# OSPLC2_2_IO4.net
KiCad netlist of a schematic drawn in Altium Designer
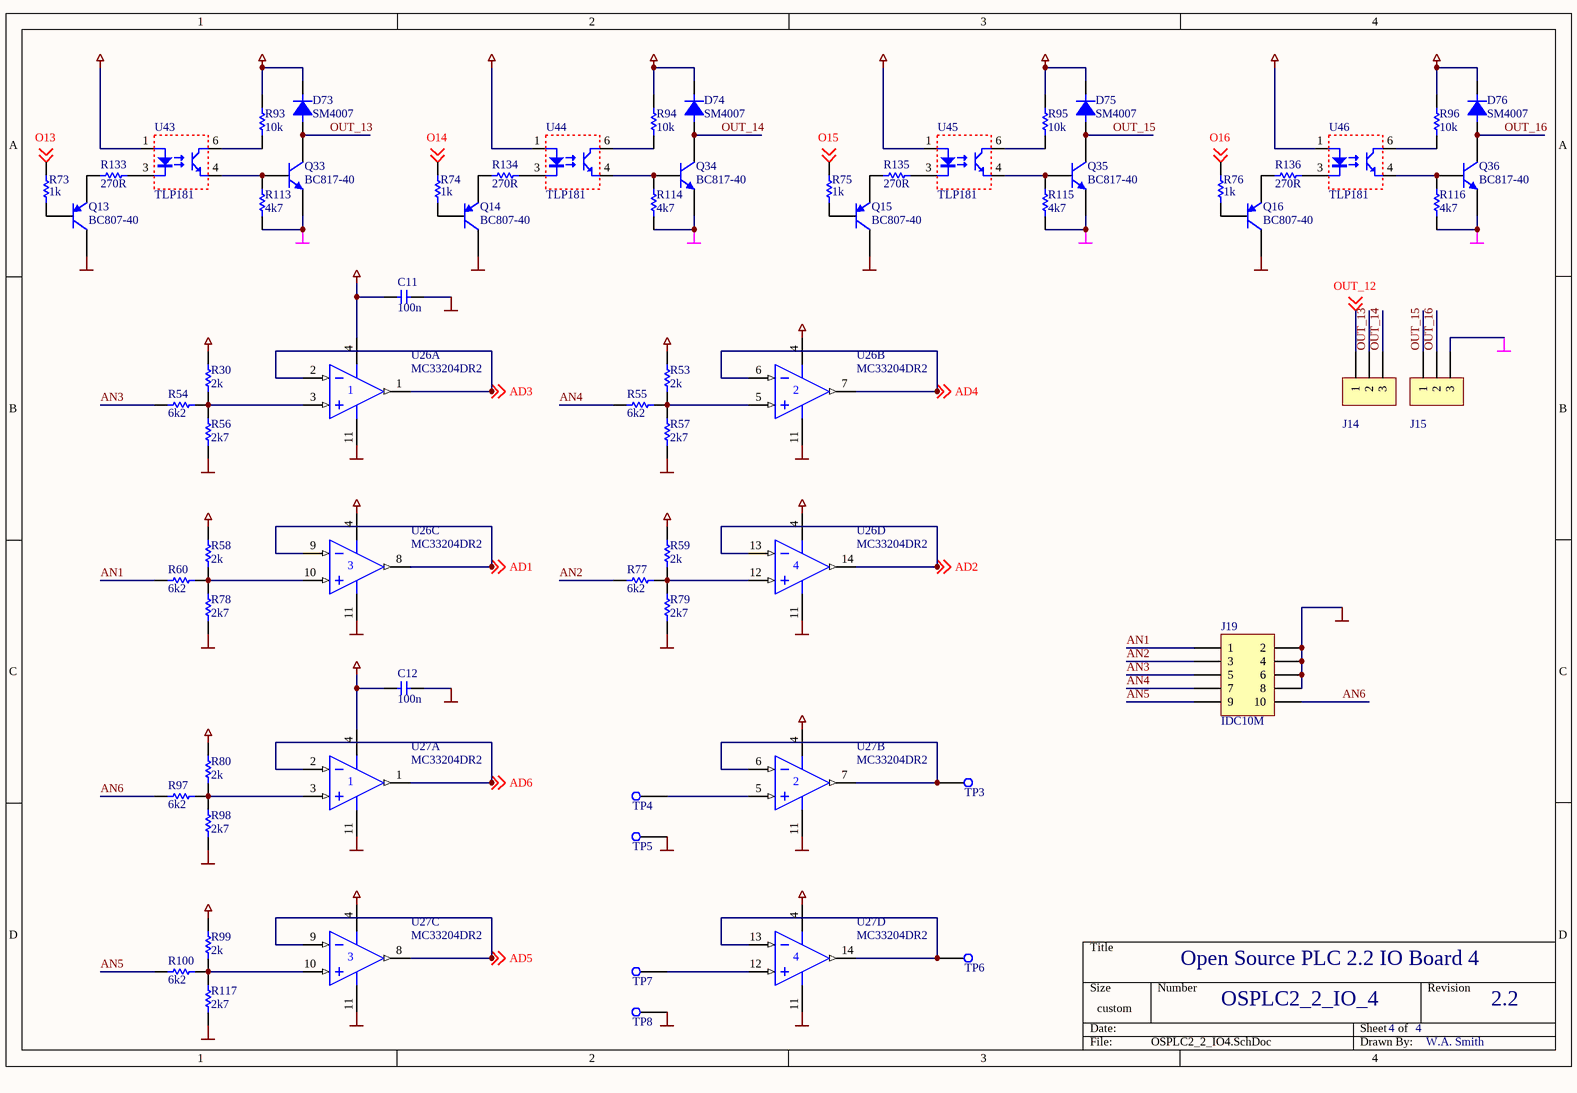
[diagram p0: OSPLC2_2_IO4.SchDoc]

(export (version "E")
  (design (tool "Eeschema 10.0.6"))
  (components
    (comp (ref "C11")
      (value "0603")
      (footprint "0603")
      (description "0603 footprint non-polorised capacitor")
      (fields (field (name "ALTIUM_VALUE") "100n"))
      (libsource (lib "Integrated Comp_lib") (part "CAP_0603"))
    )
    (comp (ref "C12")
      (value "0603")
      (footprint "0603")
      (description "0603 footprint non-polorised capacitor")
      (fields (field (name "ALTIUM_VALUE") "100n"))
      (libsource (lib "Integrated Comp_lib") (part "CAP_0603"))
    )
    (comp (ref "D73")
      (value "SM4007")
      (footprint "MELF-2.2x2.5")
      (description "1A, 1000V MELF Rectifier")
      (libsource (lib "ARM_projects") (part "SM4007"))
    )
    (comp (ref "D74")
      (value "SM4007")
      (footprint "MELF-2.2x2.5")
      (description "1A, 1000V MELF Rectifier")
      (libsource (lib "ARM_projects") (part "SM4007"))
    )
    (comp (ref "D75")
      (value "SM4007")
      (footprint "MELF-2.2x2.5")
      (description "1A, 1000V MELF Rectifier")
      (libsource (lib "ARM_projects") (part "SM4007"))
    )
    (comp (ref "D76")
      (value "SM4007")
      (footprint "MELF-2.2x2.5")
      (description "1A, 1000V MELF Rectifier")
      (libsource (lib "ARM_projects") (part "SM4007"))
    )
    (comp (ref "J14")
      (value "PCB TERMINAL")
      (footprint "TERMINAL_3WAY_5MM")
      (description "5mm spaced PCB terminal, 3 pole")
      (libsource (lib "ARM_projects") (part "TERMINAL_3WAY_5MM"))
    )
    (comp (ref "J15")
      (value "PCB TERMINAL")
      (footprint "TERMINAL_3WAY_5MM")
      (description "5mm spaced PCB terminal, 3 pole")
      (libsource (lib "ARM_projects") (part "TERMINAL_3WAY_5MM"))
    )
    (comp (ref "J19")
      (value "IDC10M")
      (footprint "IDC_10M_BOX")
      (description "10 pin IDC male connector, vertical, box")
      (libsource (lib "Integrated Comp_lib") (part "IDC_10M"))
    )
    (comp (ref "Q13")
      (value "BC807-40")
      (footprint "SO-G3/Y1")
      (description "PNP General Purpose Amplifier")
      (fields
        (field (name "MANUFACTURER") "Fairchild Semiconductor")
        (field (name "PUBLISHER") "Altium Limited")
      )
      (libsource (lib "FSC Discrete BJT") (part "BC807-40"))
    )
    (comp (ref "Q14")
      (value "BC807-40")
      (footprint "SO-G3/Y1")
      (description "PNP General Purpose Amplifier")
      (fields
        (field (name "MANUFACTURER") "Fairchild Semiconductor")
        (field (name "PUBLISHER") "Altium Limited")
      )
      (libsource (lib "FSC Discrete BJT") (part "BC807-40"))
    )
    (comp (ref "Q15")
      (value "BC807-40")
      (footprint "SO-G3/Y1")
      (description "PNP General Purpose Amplifier")
      (fields
        (field (name "MANUFACTURER") "Fairchild Semiconductor")
        (field (name "PUBLISHER") "Altium Limited")
      )
      (libsource (lib "FSC Discrete BJT") (part "BC807-40"))
    )
    (comp (ref "Q16")
      (value "BC807-40")
      (footprint "SO-G3/Y1")
      (description "PNP General Purpose Amplifier")
      (fields
        (field (name "MANUFACTURER") "Fairchild Semiconductor")
        (field (name "PUBLISHER") "Altium Limited")
      )
      (libsource (lib "FSC Discrete BJT") (part "BC807-40"))
    )
    (comp (ref "Q33")
      (value "BC817-40")
      (footprint "SO-G3/Y1")
      (description "NPN General Purpose Amplifier")
      (fields
        (field (name "MANUFACTURER") "Fairchild Semiconductor")
        (field (name "PUBLISHER") "Altium Limited")
      )
      (libsource (lib "FSC Discrete BJT") (part "BC817-40"))
    )
    (comp (ref "Q34")
      (value "BC817-40")
      (footprint "SO-G3/Y1")
      (description "NPN General Purpose Amplifier")
      (fields
        (field (name "MANUFACTURER") "Fairchild Semiconductor")
        (field (name "PUBLISHER") "Altium Limited")
      )
      (libsource (lib "FSC Discrete BJT") (part "BC817-40"))
    )
    (comp (ref "Q35")
      (value "BC817-40")
      (footprint "SO-G3/Y1")
      (description "NPN General Purpose Amplifier")
      (fields
        (field (name "MANUFACTURER") "Fairchild Semiconductor")
        (field (name "PUBLISHER") "Altium Limited")
      )
      (libsource (lib "FSC Discrete BJT") (part "BC817-40"))
    )
    (comp (ref "Q36")
      (value "BC817-40")
      (footprint "SO-G3/Y1")
      (description "NPN General Purpose Amplifier")
      (fields
        (field (name "MANUFACTURER") "Fairchild Semiconductor")
        (field (name "PUBLISHER") "Altium Limited")
      )
      (libsource (lib "FSC Discrete BJT") (part "BC817-40"))
    )
    (comp (ref "R30")
      (value "0805")
      (footprint "0805")
      (description "0805 footprint resistor")
      (fields (field (name "ALTIUM_VALUE") "2k"))
      (libsource (lib "Integrated Comp_lib") (part "RES_0805"))
    )
    (comp (ref "R53")
      (value "0805")
      (footprint "0805")
      (description "0805 footprint resistor")
      (fields (field (name "ALTIUM_VALUE") "2k"))
      (libsource (lib "Integrated Comp_lib") (part "RES_0805"))
    )
    (comp (ref "R54")
      (value "0805")
      (footprint "0805")
      (description "0805 footprint resistor")
      (fields (field (name "ALTIUM_VALUE") "6k2"))
      (libsource (lib "Integrated Comp_lib") (part "RES_0805"))
    )
    (comp (ref "R55")
      (value "0805")
      (footprint "0805")
      (description "0805 footprint resistor")
      (fields (field (name "ALTIUM_VALUE") "6k2"))
      (libsource (lib "Integrated Comp_lib") (part "RES_0805"))
    )
    (comp (ref "R56")
      (value "0805")
      (footprint "0805")
      (description "0805 footprint resistor")
      (fields (field (name "ALTIUM_VALUE") "2k7"))
      (libsource (lib "Integrated Comp_lib") (part "RES_0805"))
    )
    (comp (ref "R57")
      (value "0805")
      (footprint "0805")
      (description "0805 footprint resistor")
      (fields (field (name "ALTIUM_VALUE") "2k7"))
      (libsource (lib "Integrated Comp_lib") (part "RES_0805"))
    )
    (comp (ref "R58")
      (value "0805")
      (footprint "0805")
      (description "0805 footprint resistor")
      (fields (field (name "ALTIUM_VALUE") "2k"))
      (libsource (lib "Integrated Comp_lib") (part "RES_0805"))
    )
    (comp (ref "R59")
      (value "0805")
      (footprint "0805")
      (description "0805 footprint resistor")
      (fields (field (name "ALTIUM_VALUE") "2k"))
      (libsource (lib "Integrated Comp_lib") (part "RES_0805"))
    )
    (comp (ref "R60")
      (value "0805")
      (footprint "0805")
      (description "0805 footprint resistor")
      (fields (field (name "ALTIUM_VALUE") "6k2"))
      (libsource (lib "Integrated Comp_lib") (part "RES_0805"))
    )
    (comp (ref "R73")
      (value "0805")
      (footprint "0805")
      (description "0805 footprint resistor")
      (fields (field (name "ALTIUM_VALUE") "1k"))
      (libsource (lib "Integrated Comp_lib") (part "RES_0805"))
    )
    (comp (ref "R74")
      (value "0805")
      (footprint "0805")
      (description "0805 footprint resistor")
      (fields (field (name "ALTIUM_VALUE") "1k"))
      (libsource (lib "Integrated Comp_lib") (part "RES_0805"))
    )
    (comp (ref "R75")
      (value "0805")
      (footprint "0805")
      (description "0805 footprint resistor")
      (fields (field (name "ALTIUM_VALUE") "1k"))
      (libsource (lib "Integrated Comp_lib") (part "RES_0805"))
    )
    (comp (ref "R76")
      (value "0805")
      (footprint "0805")
      (description "0805 footprint resistor")
      (fields (field (name "ALTIUM_VALUE") "1k"))
      (libsource (lib "Integrated Comp_lib") (part "RES_0805"))
    )
    (comp (ref "R77")
      (value "0805")
      (footprint "0805")
      (description "0805 footprint resistor")
      (fields (field (name "ALTIUM_VALUE") "6k2"))
      (libsource (lib "Integrated Comp_lib") (part "RES_0805"))
    )
    (comp (ref "R78")
      (value "0805")
      (footprint "0805")
      (description "0805 footprint resistor")
      (fields (field (name "ALTIUM_VALUE") "2k7"))
      (libsource (lib "Integrated Comp_lib") (part "RES_0805"))
    )
    (comp (ref "R79")
      (value "0805")
      (footprint "0805")
      (description "0805 footprint resistor")
      (fields (field (name "ALTIUM_VALUE") "2k7"))
      (libsource (lib "Integrated Comp_lib") (part "RES_0805"))
    )
    (comp (ref "R80")
      (value "0805")
      (footprint "0805")
      (description "0805 footprint resistor")
      (fields (field (name "ALTIUM_VALUE") "2k"))
      (libsource (lib "Integrated Comp_lib") (part "RES_0805"))
    )
    (comp (ref "R93")
      (value "0805")
      (footprint "0805")
      (description "0805 footprint resistor")
      (fields (field (name "ALTIUM_VALUE") "10k"))
      (libsource (lib "Integrated Comp_lib") (part "RES_0805"))
    )
    (comp (ref "R94")
      (value "0805")
      (footprint "0805")
      (description "0805 footprint resistor")
      (fields (field (name "ALTIUM_VALUE") "10k"))
      (libsource (lib "Integrated Comp_lib") (part "RES_0805"))
    )
    (comp (ref "R95")
      (value "0805")
      (footprint "0805")
      (description "0805 footprint resistor")
      (fields (field (name "ALTIUM_VALUE") "10k"))
      (libsource (lib "Integrated Comp_lib") (part "RES_0805"))
    )
    (comp (ref "R96")
      (value "0805")
      (footprint "0805")
      (description "0805 footprint resistor")
      (fields (field (name "ALTIUM_VALUE") "10k"))
      (libsource (lib "Integrated Comp_lib") (part "RES_0805"))
    )
    (comp (ref "R97")
      (value "0805")
      (footprint "0805")
      (description "0805 footprint resistor")
      (fields (field (name "ALTIUM_VALUE") "6k2"))
      (libsource (lib "Integrated Comp_lib") (part "RES_0805"))
    )
    (comp (ref "R98")
      (value "0805")
      (footprint "0805")
      (description "0805 footprint resistor")
      (fields (field (name "ALTIUM_VALUE") "2k7"))
      (libsource (lib "Integrated Comp_lib") (part "RES_0805"))
    )
    (comp (ref "R99")
      (value "0805")
      (footprint "0805")
      (description "0805 footprint resistor")
      (fields (field (name "ALTIUM_VALUE") "2k"))
      (libsource (lib "Integrated Comp_lib") (part "RES_0805"))
    )
    (comp (ref "R100")
      (value "0805")
      (footprint "0805")
      (description "0805 footprint resistor")
      (fields (field (name "ALTIUM_VALUE") "6k2"))
      (libsource (lib "Integrated Comp_lib") (part "RES_0805"))
    )
    (comp (ref "R113")
      (value "0805")
      (footprint "0805")
      (description "0805 footprint resistor")
      (fields (field (name "ALTIUM_VALUE") "4k7"))
      (libsource (lib "Integrated Comp_lib") (part "RES_0805"))
    )
    (comp (ref "R114")
      (value "0805")
      (footprint "0805")
      (description "0805 footprint resistor")
      (fields (field (name "ALTIUM_VALUE") "4k7"))
      (libsource (lib "Integrated Comp_lib") (part "RES_0805"))
    )
    (comp (ref "R115")
      (value "0805")
      (footprint "0805")
      (description "0805 footprint resistor")
      (fields (field (name "ALTIUM_VALUE") "4k7"))
      (libsource (lib "Integrated Comp_lib") (part "RES_0805"))
    )
    (comp (ref "R116")
      (value "0805")
      (footprint "0805")
      (description "0805 footprint resistor")
      (fields (field (name "ALTIUM_VALUE") "4k7"))
      (libsource (lib "Integrated Comp_lib") (part "RES_0805"))
    )
    (comp (ref "R117")
      (value "0805")
      (footprint "0805")
      (description "0805 footprint resistor")
      (fields (field (name "ALTIUM_VALUE") "2k7"))
      (libsource (lib "Integrated Comp_lib") (part "RES_0805"))
    )
    (comp (ref "R133")
      (value "0805")
      (footprint "0805")
      (description "0805 footprint resistor")
      (fields (field (name "ALTIUM_VALUE") "270R"))
      (libsource (lib "Integrated Comp_lib") (part "RES_0805"))
    )
    (comp (ref "R134")
      (value "0805")
      (footprint "0805")
      (description "0805 footprint resistor")
      (fields (field (name "ALTIUM_VALUE") "270R"))
      (libsource (lib "Integrated Comp_lib") (part "RES_0805"))
    )
    (comp (ref "R135")
      (value "0805")
      (footprint "0805")
      (description "0805 footprint resistor")
      (fields (field (name "ALTIUM_VALUE") "270R"))
      (libsource (lib "Integrated Comp_lib") (part "RES_0805"))
    )
    (comp (ref "R136")
      (value "0805")
      (footprint "0805")
      (description "0805 footprint resistor")
      (fields (field (name "ALTIUM_VALUE") "270R"))
      (libsource (lib "Integrated Comp_lib") (part "RES_0805"))
    )
    (comp (ref "TP3")
      (value "TEST POINT")
      (footprint "TEST_POINT_TH")
      (description "Through hole test point")
      (libsource (lib "ARM_projects") (part "TEST_POINT_TH"))
    )
    (comp (ref "TP4")
      (value "TEST POINT")
      (footprint "TEST_POINT_TH")
      (description "Through hole test point")
      (libsource (lib "ARM_projects") (part "TEST_POINT_TH"))
    )
    (comp (ref "TP5")
      (value "TEST POINT")
      (footprint "TEST_POINT_TH")
      (description "Through hole test point")
      (libsource (lib "ARM_projects") (part "TEST_POINT_TH"))
    )
    (comp (ref "TP6")
      (value "TEST POINT")
      (footprint "TEST_POINT_TH")
      (description "Through hole test point")
      (libsource (lib "ARM_projects") (part "TEST_POINT_TH"))
    )
    (comp (ref "TP7")
      (value "TEST POINT")
      (footprint "TEST_POINT_TH")
      (description "Through hole test point")
      (libsource (lib "ARM_projects") (part "TEST_POINT_TH"))
    )
    (comp (ref "TP8")
      (value "TEST POINT")
      (footprint "TEST_POINT_TH")
      (description "Through hole test point")
      (libsource (lib "ARM_projects") (part "TEST_POINT_TH"))
    )
    (comp (ref "U26")
      (value "MC33204DR2")
      (footprint "SO-G14")
      (description "Rail-to-Rail Quad Operational Amplifier")
      (fields (field (name "MANUFACTURER") "Motorola") (field (name "PUBLISHER") "Altium Limited"))
      (libsource (lib "Motorola Amplifier Operational Amplifier") (part "MC33204DR2"))
    )
    (comp (ref "U27")
      (value "MC33204DR2")
      (footprint "SO-G14")
      (description "Rail-to-Rail Quad Operational Amplifier")
      (fields (field (name "MANUFACTURER") "Motorola") (field (name "PUBLISHER") "Altium Limited"))
      (libsource (lib "Motorola Amplifier Operational Amplifier") (part "MC33204DR2"))
    )
    (comp (ref "U43")
      (value "TLP181")
      (footprint "SOP4_2.54")
      (description "Toshiba Photocoupler")
      (libsource (lib "Integrated Comp_lib") (part "TLP181"))
    )
    (comp (ref "U44")
      (value "TLP181")
      (footprint "SOP4_2.54")
      (description "Toshiba Photocoupler")
      (libsource (lib "Integrated Comp_lib") (part "TLP181"))
    )
    (comp (ref "U45")
      (value "TLP181")
      (footprint "SOP4_2.54")
      (description "Toshiba Photocoupler")
      (libsource (lib "Integrated Comp_lib") (part "TLP181"))
    )
    (comp (ref "U46")
      (value "TLP181")
      (footprint "SOP4_2.54")
      (description "Toshiba Photocoupler")
      (libsource (lib "Integrated Comp_lib") (part "TLP181"))
    )
  )
  (nets
    (net (code "1") (name "/AN1") (class "Default")
      (node (ref "J19") (pin "1") (pinfunction "1_1") (pintype "passive"))
      (node (ref "R60") (pin "1") (pinfunction "1_1") (pintype "passive"))
    )
    (net (code "2") (name "/AN2") (class "Default")
      (node (ref "J19") (pin "3") (pinfunction "3_3") (pintype "passive"))
      (node (ref "R77") (pin "1") (pinfunction "1_1") (pintype "passive"))
    )
    (net (code "3") (name "/AN3") (class "Default")
      (node (ref "J19") (pin "5") (pinfunction "5_5") (pintype "passive"))
      (node (ref "R54") (pin "1") (pinfunction "1_1") (pintype "passive"))
    )
    (net (code "4") (name "/AN4") (class "Default")
      (node (ref "J19") (pin "7") (pinfunction "7_7") (pintype "passive"))
      (node (ref "R55") (pin "1") (pinfunction "1_1") (pintype "passive"))
    )
    (net (code "5") (name "/AN5") (class "Default")
      (node (ref "J19") (pin "9") (pinfunction "9_9") (pintype "passive"))
      (node (ref "R100") (pin "1") (pinfunction "1_1") (pintype "passive"))
    )
    (net (code "6") (name "/AN6") (class "Default")
      (node (ref "J19") (pin "10") (pinfunction "10_10") (pintype "passive"))
      (node (ref "R97") (pin "1") (pinfunction "1_1") (pintype "passive"))
    )
    (net (code "7") (name "/OUT_13") (class "Default")
      (node (ref "D73") (pin "1") (pinfunction "A_1") (pintype "passive"))
      (node (ref "J14") (pin "2") (pinfunction "2_2") (pintype "passive"))
      (node (ref "Q33") (pin "3") (pinfunction "C_3") (pintype "passive"))
    )
    (net (code "8") (name "/OUT_14") (class "Default")
      (node (ref "D74") (pin "1") (pinfunction "A_1") (pintype "passive"))
      (node (ref "J14") (pin "3") (pinfunction "3_3") (pintype "passive"))
      (node (ref "Q34") (pin "3") (pinfunction "C_3") (pintype "passive"))
    )
    (net (code "9") (name "/OUT_15") (class "Default")
      (node (ref "D75") (pin "1") (pinfunction "A_1") (pintype "passive"))
      (node (ref "J15") (pin "1") (pinfunction "1_1") (pintype "passive"))
      (node (ref "Q35") (pin "3") (pinfunction "C_3") (pintype "passive"))
    )
    (net (code "10") (name "/OUT_16") (class "Default")
      (node (ref "D76") (pin "1") (pinfunction "A_1") (pintype "passive"))
      (node (ref "J15") (pin "2") (pinfunction "2_2") (pintype "passive"))
      (node (ref "Q36") (pin "3") (pinfunction "C_3") (pintype "passive"))
    )
    (net (code "11") (name "AD1") (class "Default")
      (node (ref "U26") (pin "8") (pinfunction "OUT_8") (pintype "output"))
      (node (ref "U26") (pin "9") (pinfunction "IN-_9") (pintype "input"))
    )
    (net (code "12") (name "AD2") (class "Default")
      (node (ref "U26") (pin "13") (pinfunction "IN-_13") (pintype "input"))
      (node (ref "U26") (pin "14") (pinfunction "OUT_14") (pintype "output"))
    )
    (net (code "13") (name "AD3") (class "Default")
      (node (ref "U26") (pin "1") (pinfunction "OUT_1") (pintype "output"))
      (node (ref "U26") (pin "2") (pinfunction "IN-_2") (pintype "input"))
    )
    (net (code "14") (name "AD4") (class "Default")
      (node (ref "U26") (pin "6") (pinfunction "IN-_6") (pintype "input"))
      (node (ref "U26") (pin "7") (pinfunction "OUT_7") (pintype "output"))
    )
    (net (code "15") (name "AD5") (class "Default")
      (node (ref "U27") (pin "8") (pinfunction "OUT_8") (pintype "output"))
      (node (ref "U27") (pin "9") (pinfunction "IN-_9") (pintype "input"))
    )
    (net (code "16") (name "AD6") (class "Default")
      (node (ref "U27") (pin "1") (pinfunction "OUT_1") (pintype "output"))
      (node (ref "U27") (pin "2") (pinfunction "IN-_2") (pintype "input"))
    )
    (net (code "17") (name "GND") (class "Default")
      (node (ref "C11") (pin "2") (pinfunction "2_2") (pintype "passive"))
      (node (ref "C12") (pin "2") (pinfunction "2_2") (pintype "passive"))
      (node (ref "J19") (pin "2") (pinfunction "2_2") (pintype "passive"))
      (node (ref "J19") (pin "4") (pinfunction "4_4") (pintype "passive"))
      (node (ref "J19") (pin "6") (pinfunction "6_6") (pintype "passive"))
      (node (ref "J19") (pin "8") (pinfunction "8_8") (pintype "passive"))
      (node (ref "Q13") (pin "3") (pinfunction "C_3") (pintype "passive"))
      (node (ref "Q14") (pin "3") (pinfunction "C_3") (pintype "passive"))
      (node (ref "Q15") (pin "3") (pinfunction "C_3") (pintype "passive"))
      (node (ref "Q16") (pin "3") (pinfunction "C_3") (pintype "passive"))
      (node (ref "R117") (pin "1") (pinfunction "1_1") (pintype "passive"))
      (node (ref "R56") (pin "1") (pinfunction "1_1") (pintype "passive"))
      (node (ref "R57") (pin "1") (pinfunction "1_1") (pintype "passive"))
      (node (ref "R78") (pin "1") (pinfunction "1_1") (pintype "passive"))
      (node (ref "R79") (pin "1") (pinfunction "1_1") (pintype "passive"))
      (node (ref "R98") (pin "1") (pinfunction "1_1") (pintype "passive"))
      (node (ref "TP5") (pin "1") (pinfunction "1_1") (pintype "passive"))
      (node (ref "TP8") (pin "1") (pinfunction "1_1") (pintype "passive"))
      (node (ref "U26") (pin "11") (pinfunction "V-_11") (pintype "power_in"))
      (node (ref "U27") (pin "11") (pinfunction "V-_11") (pintype "power_in"))
    )
    (net (code "18") (name "Net-(Q13-B)") (class "Default")
      (node (ref "Q13") (pin "1") (pinfunction "B_1") (pintype "passive"))
      (node (ref "R73") (pin "1") (pinfunction "1_1") (pintype "passive"))
    )
    (net (code "19") (name "Net-(Q13-E)") (class "Default")
      (node (ref "Q13") (pin "2") (pinfunction "E_2") (pintype "passive"))
      (node (ref "R133") (pin "1") (pinfunction "1_1") (pintype "passive"))
    )
    (net (code "20") (name "Net-(Q14-B)") (class "Default")
      (node (ref "Q14") (pin "1") (pinfunction "B_1") (pintype "passive"))
      (node (ref "R74") (pin "1") (pinfunction "1_1") (pintype "passive"))
    )
    (net (code "21") (name "Net-(Q14-E)") (class "Default")
      (node (ref "Q14") (pin "2") (pinfunction "E_2") (pintype "passive"))
      (node (ref "R134") (pin "1") (pinfunction "1_1") (pintype "passive"))
    )
    (net (code "22") (name "Net-(Q15-B)") (class "Default")
      (node (ref "Q15") (pin "1") (pinfunction "B_1") (pintype "passive"))
      (node (ref "R75") (pin "1") (pinfunction "1_1") (pintype "passive"))
    )
    (net (code "23") (name "Net-(Q15-E)") (class "Default")
      (node (ref "Q15") (pin "2") (pinfunction "E_2") (pintype "passive"))
      (node (ref "R135") (pin "1") (pinfunction "1_1") (pintype "passive"))
    )
    (net (code "24") (name "Net-(Q16-B)") (class "Default")
      (node (ref "Q16") (pin "1") (pinfunction "B_1") (pintype "passive"))
      (node (ref "R76") (pin "1") (pinfunction "1_1") (pintype "passive"))
    )
    (net (code "25") (name "Net-(Q16-E)") (class "Default")
      (node (ref "Q16") (pin "2") (pinfunction "E_2") (pintype "passive"))
      (node (ref "R136") (pin "1") (pinfunction "1_1") (pintype "passive"))
    )
    (net (code "26") (name "Net-(Q33-B)") (class "Default")
      (node (ref "Q33") (pin "1") (pinfunction "B_1") (pintype "passive"))
      (node (ref "R113") (pin "2") (pinfunction "2_2") (pintype "passive"))
      (node (ref "U43") (pin "4") (pinfunction "4_4") (pintype "passive"))
    )
    (net (code "27") (name "Net-(Q34-B)") (class "Default")
      (node (ref "Q34") (pin "1") (pinfunction "B_1") (pintype "passive"))
      (node (ref "R114") (pin "2") (pinfunction "2_2") (pintype "passive"))
      (node (ref "U44") (pin "4") (pinfunction "4_4") (pintype "passive"))
    )
    (net (code "28") (name "Net-(Q35-B)") (class "Default")
      (node (ref "Q35") (pin "1") (pinfunction "B_1") (pintype "passive"))
      (node (ref "R115") (pin "2") (pinfunction "2_2") (pintype "passive"))
      (node (ref "U45") (pin "4") (pinfunction "4_4") (pintype "passive"))
    )
    (net (code "29") (name "Net-(Q36-B)") (class "Default")
      (node (ref "Q36") (pin "1") (pinfunction "B_1") (pintype "passive"))
      (node (ref "R116") (pin "2") (pinfunction "2_2") (pintype "passive"))
      (node (ref "U46") (pin "4") (pinfunction "4_4") (pintype "passive"))
    )
    (net (code "30") (name "Net-(R93-Pad1)") (class "Default")
      (node (ref "R93") (pin "1") (pinfunction "1_1") (pintype "passive"))
      (node (ref "U43") (pin "6") (pinfunction "6_6") (pintype "passive"))
    )
    (net (code "31") (name "Net-(R94-Pad1)") (class "Default")
      (node (ref "R94") (pin "1") (pinfunction "1_1") (pintype "passive"))
      (node (ref "U44") (pin "6") (pinfunction "6_6") (pintype "passive"))
    )
    (net (code "32") (name "Net-(R95-Pad1)") (class "Default")
      (node (ref "R95") (pin "1") (pinfunction "1_1") (pintype "passive"))
      (node (ref "U45") (pin "6") (pinfunction "6_6") (pintype "passive"))
    )
    (net (code "33") (name "Net-(R96-Pad1)") (class "Default")
      (node (ref "R96") (pin "1") (pinfunction "1_1") (pintype "passive"))
      (node (ref "U46") (pin "6") (pinfunction "6_6") (pintype "passive"))
    )
    (net (code "34") (name "Net-(R133-Pad2)") (class "Default")
      (node (ref "R133") (pin "2") (pinfunction "2_2") (pintype "passive"))
      (node (ref "U43") (pin "3") (pinfunction "3_3") (pintype "passive"))
    )
    (net (code "35") (name "Net-(R134-Pad2)") (class "Default")
      (node (ref "R134") (pin "2") (pinfunction "2_2") (pintype "passive"))
      (node (ref "U44") (pin "3") (pinfunction "3_3") (pintype "passive"))
    )
    (net (code "36") (name "Net-(R135-Pad2)") (class "Default")
      (node (ref "R135") (pin "2") (pinfunction "2_2") (pintype "passive"))
      (node (ref "U45") (pin "3") (pinfunction "3_3") (pintype "passive"))
    )
    (net (code "37") (name "Net-(R136-Pad2)") (class "Default")
      (node (ref "R136") (pin "2") (pinfunction "2_2") (pintype "passive"))
      (node (ref "U46") (pin "3") (pinfunction "3_3") (pintype "passive"))
    )
    (net (code "38") (name "Net-(U26A-IN+)") (class "Default")
      (node (ref "R30") (pin "1") (pinfunction "1_1") (pintype "passive"))
      (node (ref "R54") (pin "2") (pinfunction "2_2") (pintype "passive"))
      (node (ref "R56") (pin "2") (pinfunction "2_2") (pintype "passive"))
      (node (ref "U26") (pin "3") (pinfunction "IN+_3") (pintype "input"))
    )
    (net (code "39") (name "Net-(U26B-IN+)") (class "Default")
      (node (ref "R53") (pin "1") (pinfunction "1_1") (pintype "passive"))
      (node (ref "R55") (pin "2") (pinfunction "2_2") (pintype "passive"))
      (node (ref "R57") (pin "2") (pinfunction "2_2") (pintype "passive"))
      (node (ref "U26") (pin "5") (pinfunction "IN+_5") (pintype "input"))
    )
    (net (code "40") (name "Net-(U26C-IN+)") (class "Default")
      (node (ref "R58") (pin "1") (pinfunction "1_1") (pintype "passive"))
      (node (ref "R60") (pin "2") (pinfunction "2_2") (pintype "passive"))
      (node (ref "R78") (pin "2") (pinfunction "2_2") (pintype "passive"))
      (node (ref "U26") (pin "10") (pinfunction "IN+_10") (pintype "input"))
    )
    (net (code "41") (name "Net-(U26D-IN+)") (class "Default")
      (node (ref "R59") (pin "1") (pinfunction "1_1") (pintype "passive"))
      (node (ref "R77") (pin "2") (pinfunction "2_2") (pintype "passive"))
      (node (ref "R79") (pin "2") (pinfunction "2_2") (pintype "passive"))
      (node (ref "U26") (pin "12") (pinfunction "IN+_12") (pintype "input"))
    )
    (net (code "42") (name "Net-(U27A-IN+)") (class "Default")
      (node (ref "R80") (pin "1") (pinfunction "1_1") (pintype "passive"))
      (node (ref "R97") (pin "2") (pinfunction "2_2") (pintype "passive"))
      (node (ref "R98") (pin "2") (pinfunction "2_2") (pintype "passive"))
      (node (ref "U27") (pin "3") (pinfunction "IN+_3") (pintype "input"))
    )
    (net (code "43") (name "Net-(U27B-IN+)") (class "Default")
      (node (ref "TP4") (pin "1") (pinfunction "1_1") (pintype "passive"))
      (node (ref "U27") (pin "5") (pinfunction "IN+_5") (pintype "input"))
    )
    (net (code "44") (name "Net-(U27B-IN-)") (class "Default")
      (node (ref "TP3") (pin "1") (pinfunction "1_1") (pintype "passive"))
      (node (ref "U27") (pin "6") (pinfunction "IN-_6") (pintype "input"))
      (node (ref "U27") (pin "7") (pinfunction "OUT_7") (pintype "output"))
    )
    (net (code "45") (name "Net-(U27C-IN+)") (class "Default")
      (node (ref "R100") (pin "2") (pinfunction "2_2") (pintype "passive"))
      (node (ref "R117") (pin "2") (pinfunction "2_2") (pintype "passive"))
      (node (ref "R99") (pin "1") (pinfunction "1_1") (pintype "passive"))
      (node (ref "U27") (pin "10") (pinfunction "IN+_10") (pintype "input"))
    )
    (net (code "46") (name "Net-(U27D-IN+)") (class "Default")
      (node (ref "TP7") (pin "1") (pinfunction "1_1") (pintype "passive"))
      (node (ref "U27") (pin "12") (pinfunction "IN+_12") (pintype "input"))
    )
    (net (code "47") (name "Net-(U27D-IN-)") (class "Default")
      (node (ref "TP6") (pin "1") (pinfunction "1_1") (pintype "passive"))
      (node (ref "U27") (pin "13") (pinfunction "IN-_13") (pintype "input"))
      (node (ref "U27") (pin "14") (pinfunction "OUT_14") (pintype "output"))
    )
    (net (code "48") (name "O13") (class "Default")
      (node (ref "R73") (pin "2") (pinfunction "2_2") (pintype "passive"))
    )
    (net (code "49") (name "O14") (class "Default")
      (node (ref "R74") (pin "2") (pinfunction "2_2") (pintype "passive"))
    )
    (net (code "50") (name "O15") (class "Default")
      (node (ref "R75") (pin "2") (pinfunction "2_2") (pintype "passive"))
    )
    (net (code "51") (name "O16") (class "Default")
      (node (ref "R76") (pin "2") (pinfunction "2_2") (pintype "passive"))
    )
    (net (code "52") (name "OUT_12") (class "Default")
      (node (ref "J14") (pin "1") (pinfunction "1_1") (pintype "passive"))
    )
    (net (code "53") (name "OUT_GND") (class "Default")
      (node (ref "J15") (pin "3") (pinfunction "3_3") (pintype "passive"))
      (node (ref "Q33") (pin "2") (pinfunction "E_2") (pintype "passive"))
      (node (ref "Q34") (pin "2") (pinfunction "E_2") (pintype "passive"))
      (node (ref "Q35") (pin "2") (pinfunction "E_2") (pintype "passive"))
      (node (ref "Q36") (pin "2") (pinfunction "E_2") (pintype "passive"))
      (node (ref "R113") (pin "1") (pinfunction "1_1") (pintype "passive"))
      (node (ref "R114") (pin "1") (pinfunction "1_1") (pintype "passive"))
      (node (ref "R115") (pin "1") (pinfunction "1_1") (pintype "passive"))
      (node (ref "R116") (pin "1") (pinfunction "1_1") (pintype "passive"))
    )
    (net (code "54") (name "VCC3v3") (class "Default")
      (node (ref "C11") (pin "1") (pinfunction "1_1") (pintype "passive"))
      (node (ref "C12") (pin "1") (pinfunction "1_1") (pintype "passive"))
      (node (ref "R30") (pin "2") (pinfunction "2_2") (pintype "passive"))
      (node (ref "R53") (pin "2") (pinfunction "2_2") (pintype "passive"))
      (node (ref "R58") (pin "2") (pinfunction "2_2") (pintype "passive"))
      (node (ref "R59") (pin "2") (pinfunction "2_2") (pintype "passive"))
      (node (ref "R80") (pin "2") (pinfunction "2_2") (pintype "passive"))
      (node (ref "R99") (pin "2") (pinfunction "2_2") (pintype "passive"))
      (node (ref "U26") (pin "4") (pinfunction "V+_4") (pintype "power_in"))
      (node (ref "U27") (pin "4") (pinfunction "V+_4") (pintype "power_in"))
      (node (ref "U43") (pin "1") (pinfunction "1_1") (pintype "passive"))
      (node (ref "U44") (pin "1") (pinfunction "1_1") (pintype "passive"))
      (node (ref "U45") (pin "1") (pinfunction "1_1") (pintype "passive"))
      (node (ref "U46") (pin "1") (pinfunction "1_1") (pintype "passive"))
    )
    (net (code "55") (name "VCC24") (class "Default")
      (node (ref "D73") (pin "2") (pinfunction "C_2") (pintype "passive"))
      (node (ref "D74") (pin "2") (pinfunction "C_2") (pintype "passive"))
      (node (ref "D75") (pin "2") (pinfunction "C_2") (pintype "passive"))
      (node (ref "D76") (pin "2") (pinfunction "C_2") (pintype "passive"))
      (node (ref "R93") (pin "2") (pinfunction "2_2") (pintype "passive"))
      (node (ref "R94") (pin "2") (pinfunction "2_2") (pintype "passive"))
      (node (ref "R95") (pin "2") (pinfunction "2_2") (pintype "passive"))
      (node (ref "R96") (pin "2") (pinfunction "2_2") (pintype "passive"))
    )
  )
)
